# PCI_Express.net
KiCad netlist of a schematic drawn in Altium Designer
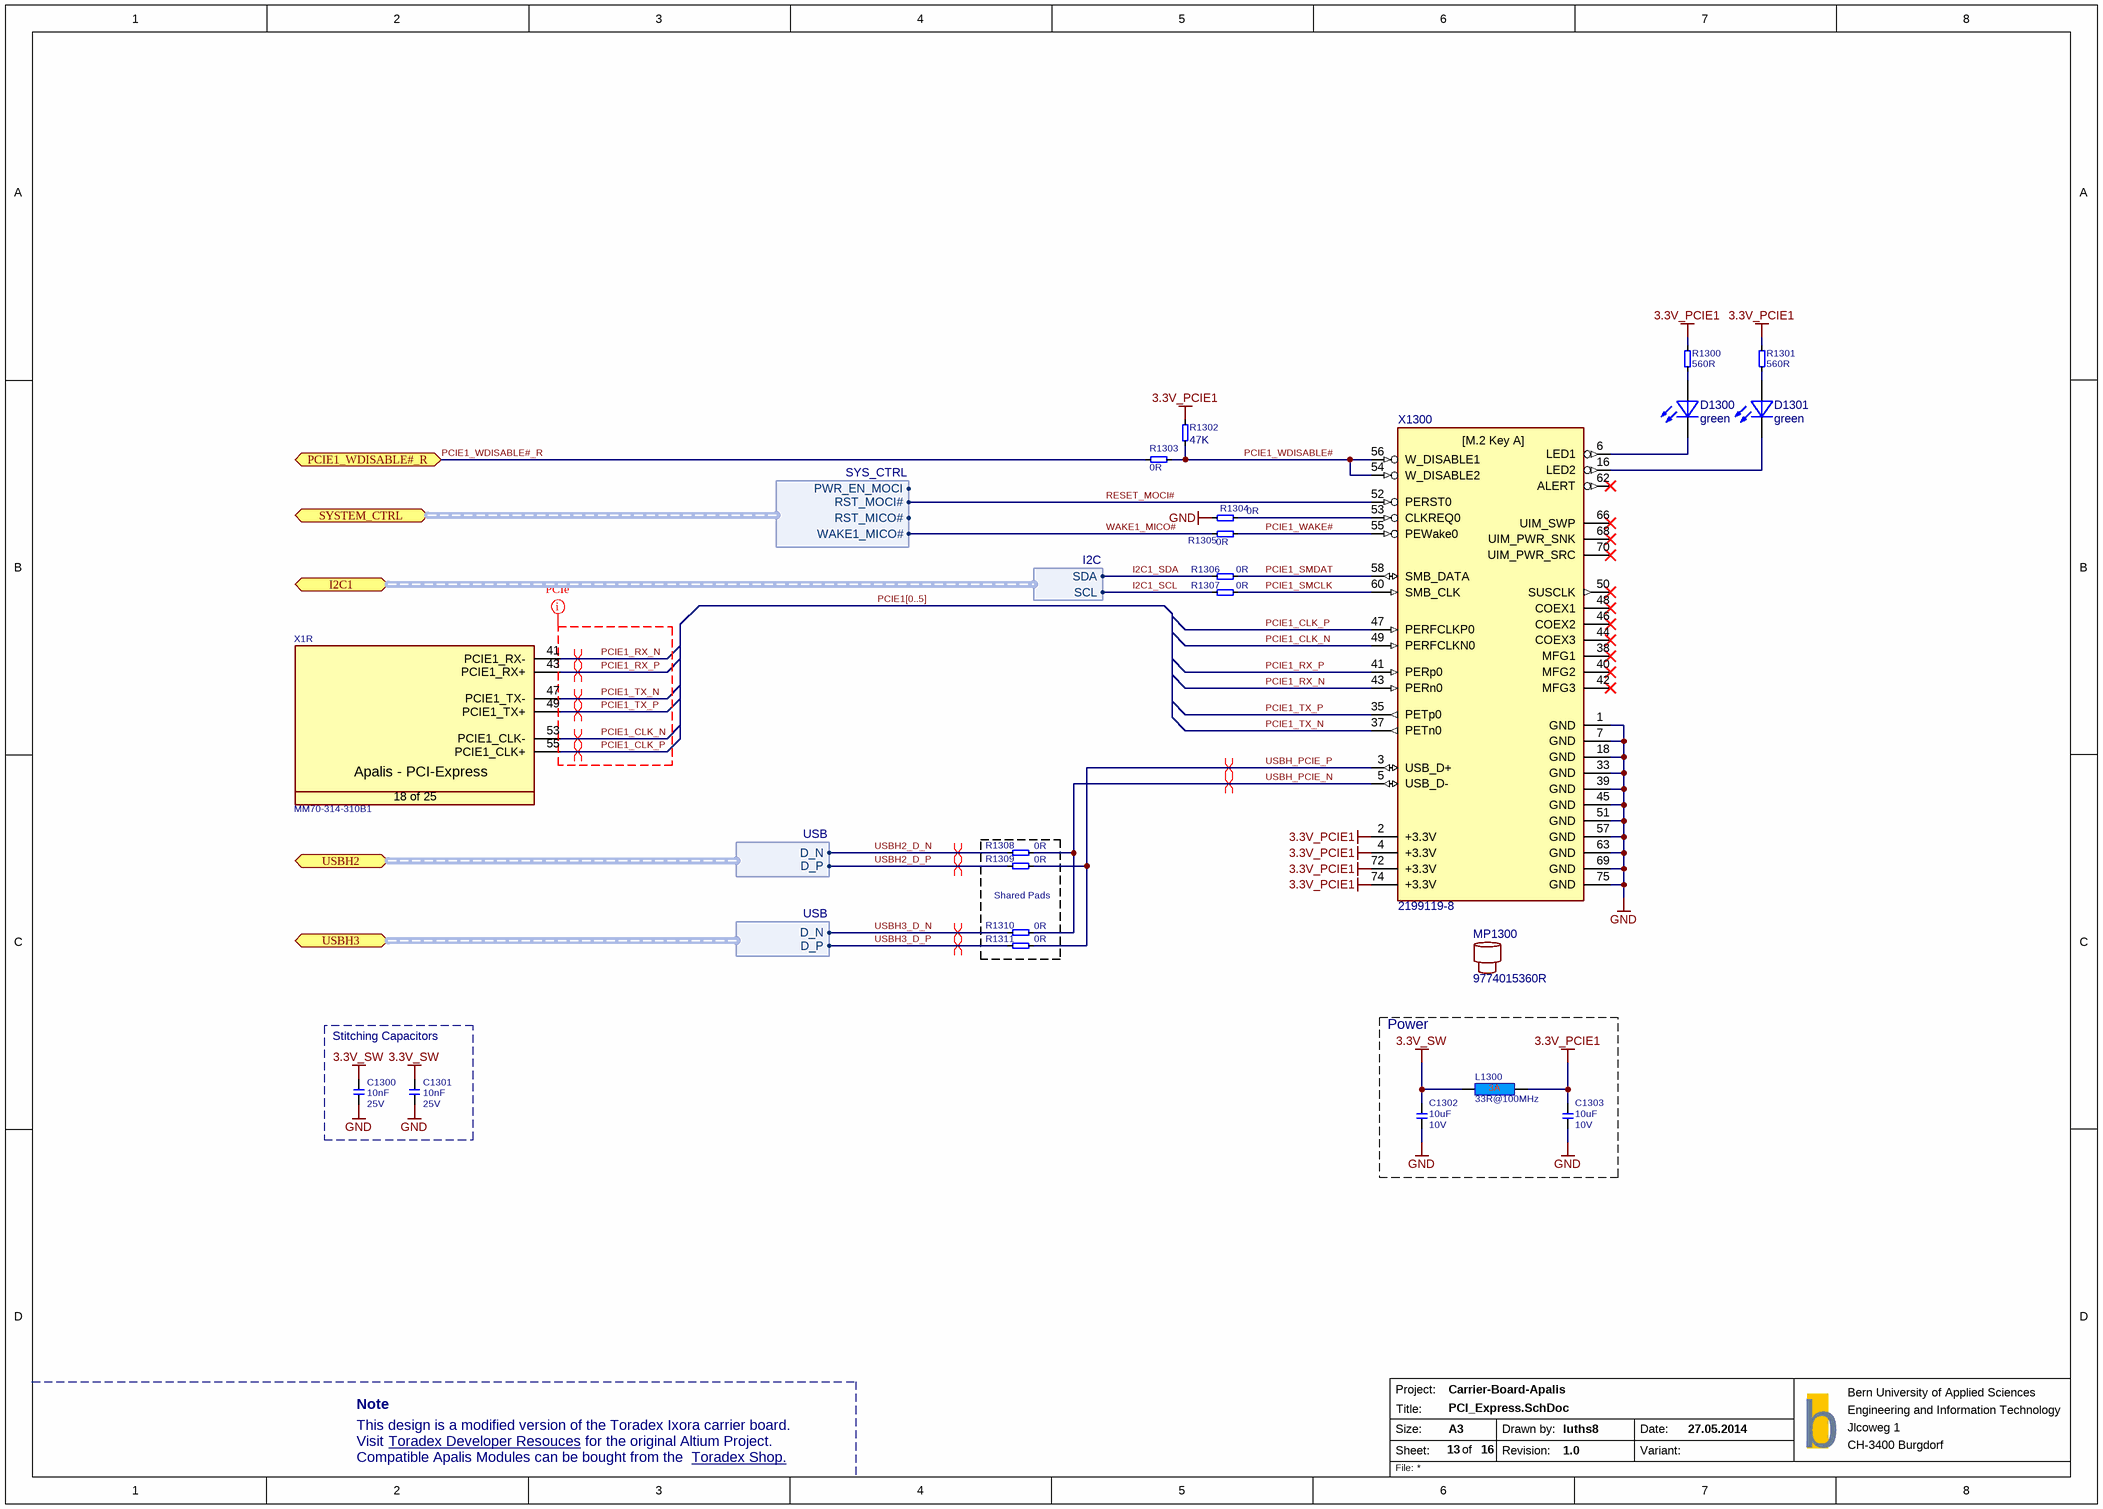
[diagram p0: PCI_Express.SchDoc]

(export (version "E")
  (design (tool "Eeschema 10.0.6"))
  (components
    (comp (ref "C1300")
      (value "10nF")
      (footprint "SMD0603CAP")
      (description "Capacitor Ceramic X7R 10nF 25V 10% 0603")
      (fields (field (name "TOLERANCE") "10%") (field (name "RATING") "25V"))
      (libsource (lib "Ixora") (part "C-X7R-10nF-25V-10%-0603"))
    )
    (comp (ref "C1301")
      (value "10nF")
      (footprint "SMD0603CAP")
      (description "Capacitor Ceramic X7R 10nF 25V 10% 0603")
      (fields (field (name "TOLERANCE") "10%") (field (name "RATING") "25V"))
      (libsource (lib "Ixora") (part "C-X7R-10nF-25V-10%-0603"))
    )
    (comp (ref "C1302")
      (value "10uF")
      (footprint "SMD0603CAP")
      (description "Capacitor Ceramic X5R 10uF 10V 20% 0603")
      (fields (field (name "TOLERANCE") "20%") (field (name "RATING") "10V"))
      (libsource (lib "Ixora") (part "C-X5R-10uF-10V-20%-0603"))
    )
    (comp (ref "C1303")
      (value "10uF")
      (footprint "SMD0603CAP")
      (description "Capacitor Ceramic X5R 10uF 10V 20% 0603")
      (fields (field (name "TOLERANCE") "20%") (field (name "RATING") "10V"))
      (libsource (lib "Ixora") (part "C-X5R-10uF-10V-20%-0603"))
    )
    (comp (ref "D1300")
      (value "green")
      (footprint "LED")
      (description "LED green")
      (fields (field (name "MANUFACTURER PART NO.") "LGM67KG1J224Z"))
      (libsource (lib "Audio-Streamer") (part "LED green"))
    )
    (comp (ref "D1301")
      (value "green")
      (footprint "LED")
      (description "LED green")
      (fields (field (name "MANUFACTURER PART NO.") "LGM67KG1J224Z"))
      (libsource (lib "Audio-Streamer") (part "LED green"))
    )
    (comp (ref "L1300")
      (value "33R@100MHz")
      (footprint "INDC1608X95N")
      (description "33R@100MHz 3A EMI FILTER")
      (fields (field (name "TOLERANCE") "25%"))
      (libsource (lib "Ixora") (part "L-33R@100MHz-3A-25%-0603"))
    )
    (comp (ref "MP1300")
      (value "9774015360R")
      (description "Spacer M3 SMD")
      (libsource (lib "Audio-Streamer") (part "Spacer M3 SMD"))
    )
    (comp (ref "R1300")
      (value "560R")
      (footprint "SMD0603RES")
      (description "Resistor 560 ohm 63mW 5% 0603")
      (fields (field (name "TOLERANCE") "5%"))
      (libsource (lib "Ixora") (part "R-560R-63mW-5%-0402"))
    )
    (comp (ref "R1301")
      (value "560R")
      (footprint "SMD0603RES")
      (description "Resistor 560 ohm 63mW 5% 0603")
      (fields (field (name "TOLERANCE") "5%"))
      (libsource (lib "Ixora") (part "R-560R-63mW-5%-0402"))
    )
    (comp (ref "R1302")
      (value "47K")
      (footprint "SMD0603RES")
      (description "Resistor 47 Kohm 63mW 5% 0603")
      (fields (field (name "TOLERANCE") "5%"))
      (libsource (lib "Ixora") (part "R-47KR-63mW-5%-0603"))
    )
    (comp (ref "R1303")
      (value "0R")
      (footprint "SMD0603RES")
      (description "Resistor 0 ohm 63mW 1% 0603")
      (fields (field (name "TOLERANCE") "1%"))
      (libsource (lib "Ixora") (part "R-0R-63mW-1%-0603"))
    )
    (comp (ref "R1304")
      (value "0R")
      (footprint "SMD0603RES")
      (description "Resistor 0 ohm 63mW 1% 0603")
      (fields (field (name "TOLERANCE") "1%"))
      (libsource (lib "Ixora") (part "R-0R-63mW-1%-0603"))
    )
    (comp (ref "R1305")
      (value "0R")
      (footprint "SMD0603RES")
      (description "Resistor 0 ohm 63mW 1% 0603")
      (fields (field (name "TOLERANCE") "1%"))
      (libsource (lib "Ixora") (part "R-0R-63mW-1%-0603"))
    )
    (comp (ref "R1306")
      (value "0R")
      (footprint "SMD0603RES")
      (description "Resistor 0 ohm 63mW 1% 0603")
      (fields (field (name "TOLERANCE") "1%"))
      (libsource (lib "Ixora") (part "R-0R-63mW-1%-0402"))
    )
    (comp (ref "R1307")
      (value "0R")
      (footprint "SMD0603RES")
      (description "Resistor 0 ohm 63mW 1% 0603")
      (fields (field (name "TOLERANCE") "1%"))
      (libsource (lib "Ixora") (part "R-0R-63mW-1%-0402"))
    )
    (comp (ref "R1308")
      (value "0R")
      (footprint "SMD0603RES")
      (description "Resistor 0 ohm 63mW 1% 0603")
      (fields (field (name "TOLERANCE") "1%"))
      (libsource (lib "Ixora") (part "R-0R-63mW-1%-0603"))
    )
    (comp (ref "R1309")
      (value "0R")
      (footprint "SMD0603RES")
      (description "Resistor 0 ohm 63mW 1% 0603")
      (fields (field (name "TOLERANCE") "1%"))
      (libsource (lib "Ixora") (part "R-0R-63mW-1%-0603"))
    )
    (comp (ref "R1310")
      (value "0R")
      (footprint "SMD0603RES")
      (description "Resistor 0 ohm 63mW 1% 0603")
      (fields (field (name "TOLERANCE") "1%"))
      (libsource (lib "Ixora") (part "R-0R-63mW-1%-0603"))
    )
    (comp (ref "R1311")
      (value "0R")
      (footprint "SMD0603RES")
      (description "Resistor 0 ohm 63mW 1% 0603")
      (fields (field (name "TOLERANCE") "1%"))
      (libsource (lib "Ixora") (part "R-0R-63mW-1%-0603"))
    )
    (comp (ref "X1")
      (value "CON-JAE-MM70-314-310B1-314-0.5mm")
      (footprint "T_JAE_MM70-314-310B1")
      (description "MXM3 Connector")
      (fields (field (name "MANUFACTURER PART NO.") "MM70-314-310B1"))
      (libsource (lib "Ixora") (part "CON-JAE-MM70-314-310B1-314-0.5mm"))
    )
    (comp (ref "X1300")
      (value "2199119-8")
      (footprint "2199119-8-KEY-A-2230")
      (description "Connector M.2 Key A")
      (libsource (lib "Audio-Streamer") (part "Connector M.2 Key A"))
    )
  )
  (nets
    (net (code "10") (name "/I2C1_SCL") (class "Default")
      (node (ref "R1307") (pin "1") (pinfunction "1_1") (pintype "passive"))
    )
    (net (code "11") (name "/I2C1_SDA") (class "Default")
      (node (ref "R1306") (pin "1") (pinfunction "1_1") (pintype "passive"))
    )
    (net (code "13") (name "/PCIE1_CLK_N") (class "Default")
      (node (ref "X1") (pin "53") (pinfunction "PCIE1_CLK-_53") (pintype "passive"))
      (node (ref "X1300") (pin "49") (pinfunction "PERFCLKN0_49") (pintype "input"))
    )
    (net (code "14") (name "/PCIE1_CLK_P") (class "Default")
      (node (ref "X1") (pin "55") (pinfunction "PCIE1_CLK+_55") (pintype "passive"))
      (node (ref "X1300") (pin "47") (pinfunction "PERFCLKP0_47") (pintype "input"))
    )
    (net (code "15") (name "/PCIE1_RX_N") (class "Default")
      (node (ref "X1") (pin "41") (pinfunction "PCIE1_RX-_41") (pintype "passive"))
      (node (ref "X1300") (pin "43") (pinfunction "PERn0_43") (pintype "input"))
    )
    (net (code "16") (name "/PCIE1_RX_P") (class "Default")
      (node (ref "X1") (pin "43") (pinfunction "PCIE1_RX+_43") (pintype "passive"))
      (node (ref "X1300") (pin "41") (pinfunction "PERp0_41") (pintype "input"))
    )
    (net (code "17") (name "/PCIE1_SMCLK") (class "Default")
      (node (ref "R1307") (pin "2") (pinfunction "2_2") (pintype "passive"))
      (node (ref "X1300") (pin "60") (pinfunction "SMB_CLK_60") (pintype "input"))
    )
    (net (code "18") (name "/PCIE1_SMDAT") (class "Default")
      (node (ref "R1306") (pin "2") (pinfunction "2_2") (pintype "passive"))
      (node (ref "X1300") (pin "58") (pinfunction "SMB_DATA_58") (pintype "bidirectional"))
    )
    (net (code "19") (name "/PCIE1_TX_N") (class "Default")
      (node (ref "X1") (pin "47") (pinfunction "PCIE1_TX-_47") (pintype "passive"))
      (node (ref "X1300") (pin "37") (pinfunction "PETn0_37") (pintype "output"))
    )
    (net (code "20") (name "/PCIE1_TX_P") (class "Default")
      (node (ref "X1") (pin "49") (pinfunction "PCIE1_TX+_49") (pintype "passive"))
      (node (ref "X1300") (pin "35") (pinfunction "PETp0_35") (pintype "output"))
    )
    (net (code "21") (name "/PCIE1_WAKE#") (class "Default")
      (node (ref "R1305") (pin "2") (pinfunction "2_2") (pintype "passive"))
      (node (ref "X1300") (pin "55") (pinfunction "PEWake0_55") (pintype "input"))
    )
    (net (code "22") (name "/PCIE1_WDISABLE#") (class "Default")
      (node (ref "R1302") (pin "1") (pinfunction "1_1") (pintype "passive"))
      (node (ref "R1303") (pin "1") (pinfunction "1_1") (pintype "passive"))
      (node (ref "X1300") (pin "54") (pinfunction "W_DISABLE2_54") (pintype "input"))
      (node (ref "X1300") (pin "56") (pinfunction "W_DISABLE1_56") (pintype "input"))
    )
    (net (code "23") (name "/PCIE1_WDISABLE#_R") (class "Default")
      (node (ref "R1303") (pin "2") (pinfunction "2_2") (pintype "passive"))
    )
    (net (code "24") (name "/RESET_MOCI#") (class "Default")
      (node (ref "X1300") (pin "52") (pinfunction "PERST0_52") (pintype "input"))
    )
    (net (code "27") (name "/USBH3_D_N") (class "Default")
      (node (ref "R1310") (pin "1") (pinfunction "1_1") (pintype "passive"))
    )
    (net (code "28") (name "/USBH3_D_P") (class "Default")
      (node (ref "R1311") (pin "1") (pinfunction "1_1") (pintype "passive"))
    )
    (net (code "29") (name "/USBH_PCIE_N") (class "Default")
      (node (ref "R1308") (pin "2") (pinfunction "2_2") (pintype "passive"))
      (node (ref "R1310") (pin "2") (pinfunction "2_2") (pintype "passive"))
      (node (ref "X1300") (pin "5") (pinfunction "USB_D-_5") (pintype "bidirectional"))
    )
    (net (code "30") (name "/USBH_PCIE_P") (class "Default")
      (node (ref "R1309") (pin "2") (pinfunction "2_2") (pintype "passive"))
      (node (ref "R1311") (pin "2") (pinfunction "2_2") (pintype "passive"))
      (node (ref "X1300") (pin "3") (pinfunction "USB_D+_3") (pintype "bidirectional"))
    )
    (net (code "31") (name "/WAKE1_MICO#") (class "Default")
      (node (ref "R1305") (pin "1") (pinfunction "1_1") (pintype "passive"))
    )
    (net (code "35") (name "3.3V_PCIE1") (class "Default")
      (node (ref "C1303") (pin "2") (pinfunction "2_2") (pintype "passive"))
      (node (ref "L1300") (pin "2") (pinfunction "2_2") (pintype "passive"))
      (node (ref "R1300") (pin "1") (pinfunction "1_1") (pintype "passive"))
      (node (ref "R1301") (pin "1") (pinfunction "1_1") (pintype "passive"))
      (node (ref "R1302") (pin "2") (pinfunction "2_2") (pintype "passive"))
      (node (ref "X1300") (pin "2") (pinfunction "+3.3V_2") (pintype "power_in"))
      (node (ref "X1300") (pin "4") (pinfunction "+3.3V_4") (pintype "power_in"))
      (node (ref "X1300") (pin "72") (pinfunction "+3.3V_72") (pintype "power_in"))
      (node (ref "X1300") (pin "74") (pinfunction "+3.3V_74") (pintype "power_in"))
    )
    (net (code "36") (name "3.3V_SW") (class "Default")
      (node (ref "C1300") (pin "2") (pinfunction "2_2") (pintype "passive"))
      (node (ref "C1301") (pin "2") (pinfunction "2_2") (pintype "passive"))
      (node (ref "C1302") (pin "2") (pinfunction "2_2") (pintype "passive"))
      (node (ref "L1300") (pin "1") (pinfunction "1_1") (pintype "passive"))
    )
    (net (code "37") (name "GND") (class "Default")
      (node (ref "C1300") (pin "1") (pinfunction "1_1") (pintype "passive"))
      (node (ref "C1301") (pin "1") (pinfunction "1_1") (pintype "passive"))
      (node (ref "C1302") (pin "1") (pinfunction "1_1") (pintype "passive"))
      (node (ref "C1303") (pin "1") (pinfunction "1_1") (pintype "passive"))
      (node (ref "R1304") (pin "1") (pinfunction "1_1") (pintype "passive"))
      (node (ref "X1300") (pin "1") (pinfunction "GND_1") (pintype "power_in"))
      (node (ref "X1300") (pin "18") (pinfunction "GND_18") (pintype "power_in"))
      (node (ref "X1300") (pin "33") (pinfunction "GND_33") (pintype "power_in"))
      (node (ref "X1300") (pin "39") (pinfunction "GND_39") (pintype "power_in"))
      (node (ref "X1300") (pin "45") (pinfunction "GND_45") (pintype "power_in"))
      (node (ref "X1300") (pin "51") (pinfunction "GND_51") (pintype "power_in"))
      (node (ref "X1300") (pin "57") (pinfunction "GND_57") (pintype "power_in"))
      (node (ref "X1300") (pin "63") (pinfunction "GND_63") (pintype "power_in"))
      (node (ref "X1300") (pin "69") (pinfunction "GND_69") (pintype "power_in"))
      (node (ref "X1300") (pin "7") (pinfunction "GND_7") (pintype "power_in"))
      (node (ref "X1300") (pin "75") (pinfunction "GND_75") (pintype "power_in"))
    )
    (net (code "38") (name "Net-(D1300-PadA)") (class "Default")
      (node (ref "D1300") (pin "A") (pinfunction "A_A") (pintype "passive"))
      (node (ref "R1300") (pin "2") (pinfunction "2_2") (pintype "passive"))
    )
    (net (code "39") (name "Net-(D1301-PadA)") (class "Default")
      (node (ref "D1301") (pin "A") (pinfunction "A_A") (pintype "passive"))
      (node (ref "R1301") (pin "2") (pinfunction "2_2") (pintype "passive"))
    )
    (net (code "40") (name "Net-(X1300-CLKREQ0)") (class "Default")
      (node (ref "R1304") (pin "2") (pinfunction "2_2") (pintype "passive"))
      (node (ref "X1300") (pin "53") (pinfunction "CLKREQ0_53") (pintype "input"))
    )
    (net (code "41") (name "Net-(X1300-LED1)") (class "Default")
      (node (ref "D1300") (pin "C") (pinfunction "C_C") (pintype "passive"))
      (node (ref "X1300") (pin "6") (pinfunction "LED1_6") (pintype "output"))
    )
    (net (code "42") (name "Net-(X1300-LED2)") (class "Default")
      (node (ref "D1301") (pin "C") (pinfunction "C_C") (pintype "passive"))
      (node (ref "X1300") (pin "16") (pinfunction "LED2_16") (pintype "output"))
    )
    (net (code "43") (name "unconnected-(R1308-Pad1)") (class "Default")
      (node (ref "R1308") (pin "1") (pinfunction "1_1") (pintype "passive"))
    )
    (net (code "44") (name "unconnected-(R1309-Pad1)") (class "Default")
      (node (ref "R1309") (pin "1") (pinfunction "1_1") (pintype "passive"))
    )
    (net (code "45") (name "unconnected-(X1300-ALERT-Pad62)") (class "Default")
      (node (ref "X1300") (pin "62") (pinfunction "ALERT_62") (pintype "output+no_connect"))
    )
    (net (code "46") (name "unconnected-(X1300-COEX1-Pad48)") (class "Default")
      (node (ref "X1300") (pin "48") (pinfunction "COEX1_48") (pintype "passive+no_connect"))
    )
    (net (code "47") (name "unconnected-(X1300-COEX2-Pad46)") (class "Default")
      (node (ref "X1300") (pin "46") (pinfunction "COEX2_46") (pintype "passive+no_connect"))
    )
    (net (code "48") (name "unconnected-(X1300-COEX3-Pad44)") (class "Default")
      (node (ref "X1300") (pin "44") (pinfunction "COEX3_44") (pintype "passive+no_connect"))
    )
    (net (code "49") (name "unconnected-(X1300-MFG1-Pad38)") (class "Default")
      (node (ref "X1300") (pin "38") (pinfunction "MFG1_38") (pintype "passive+no_connect"))
    )
    (net (code "50") (name "unconnected-(X1300-MFG2-Pad40)") (class "Default")
      (node (ref "X1300") (pin "40") (pinfunction "MFG2_40") (pintype "passive+no_connect"))
    )
    (net (code "51") (name "unconnected-(X1300-MFG3-Pad42)") (class "Default")
      (node (ref "X1300") (pin "42") (pinfunction "MFG3_42") (pintype "passive+no_connect"))
    )
    (net (code "52") (name "unconnected-(X1300-SUSCLK-Pad50)") (class "Default")
      (node (ref "X1300") (pin "50") (pinfunction "SUSCLK_50") (pintype "output+no_connect"))
    )
    (net (code "53") (name "unconnected-(X1300-UIM_PWR_SNK-Pad68)") (class "Default")
      (node (ref "X1300") (pin "68") (pinfunction "UIM_PWR_SNK_68") (pintype "passive+no_connect"))
    )
    (net (code "54") (name "unconnected-(X1300-UIM_PWR_SRC-Pad70)") (class "Default")
      (node (ref "X1300") (pin "70") (pinfunction "UIM_PWR_SRC_70") (pintype "passive+no_connect"))
    )
    (net (code "55") (name "unconnected-(X1300-UIM_SWP-Pad66)") (class "Default")
      (node (ref "X1300") (pin "66") (pinfunction "UIM_SWP_66") (pintype "passive+no_connect"))
    )
  )
)
